# merope-power.net
KiCad netlist of a schematic drawn in EAGLE
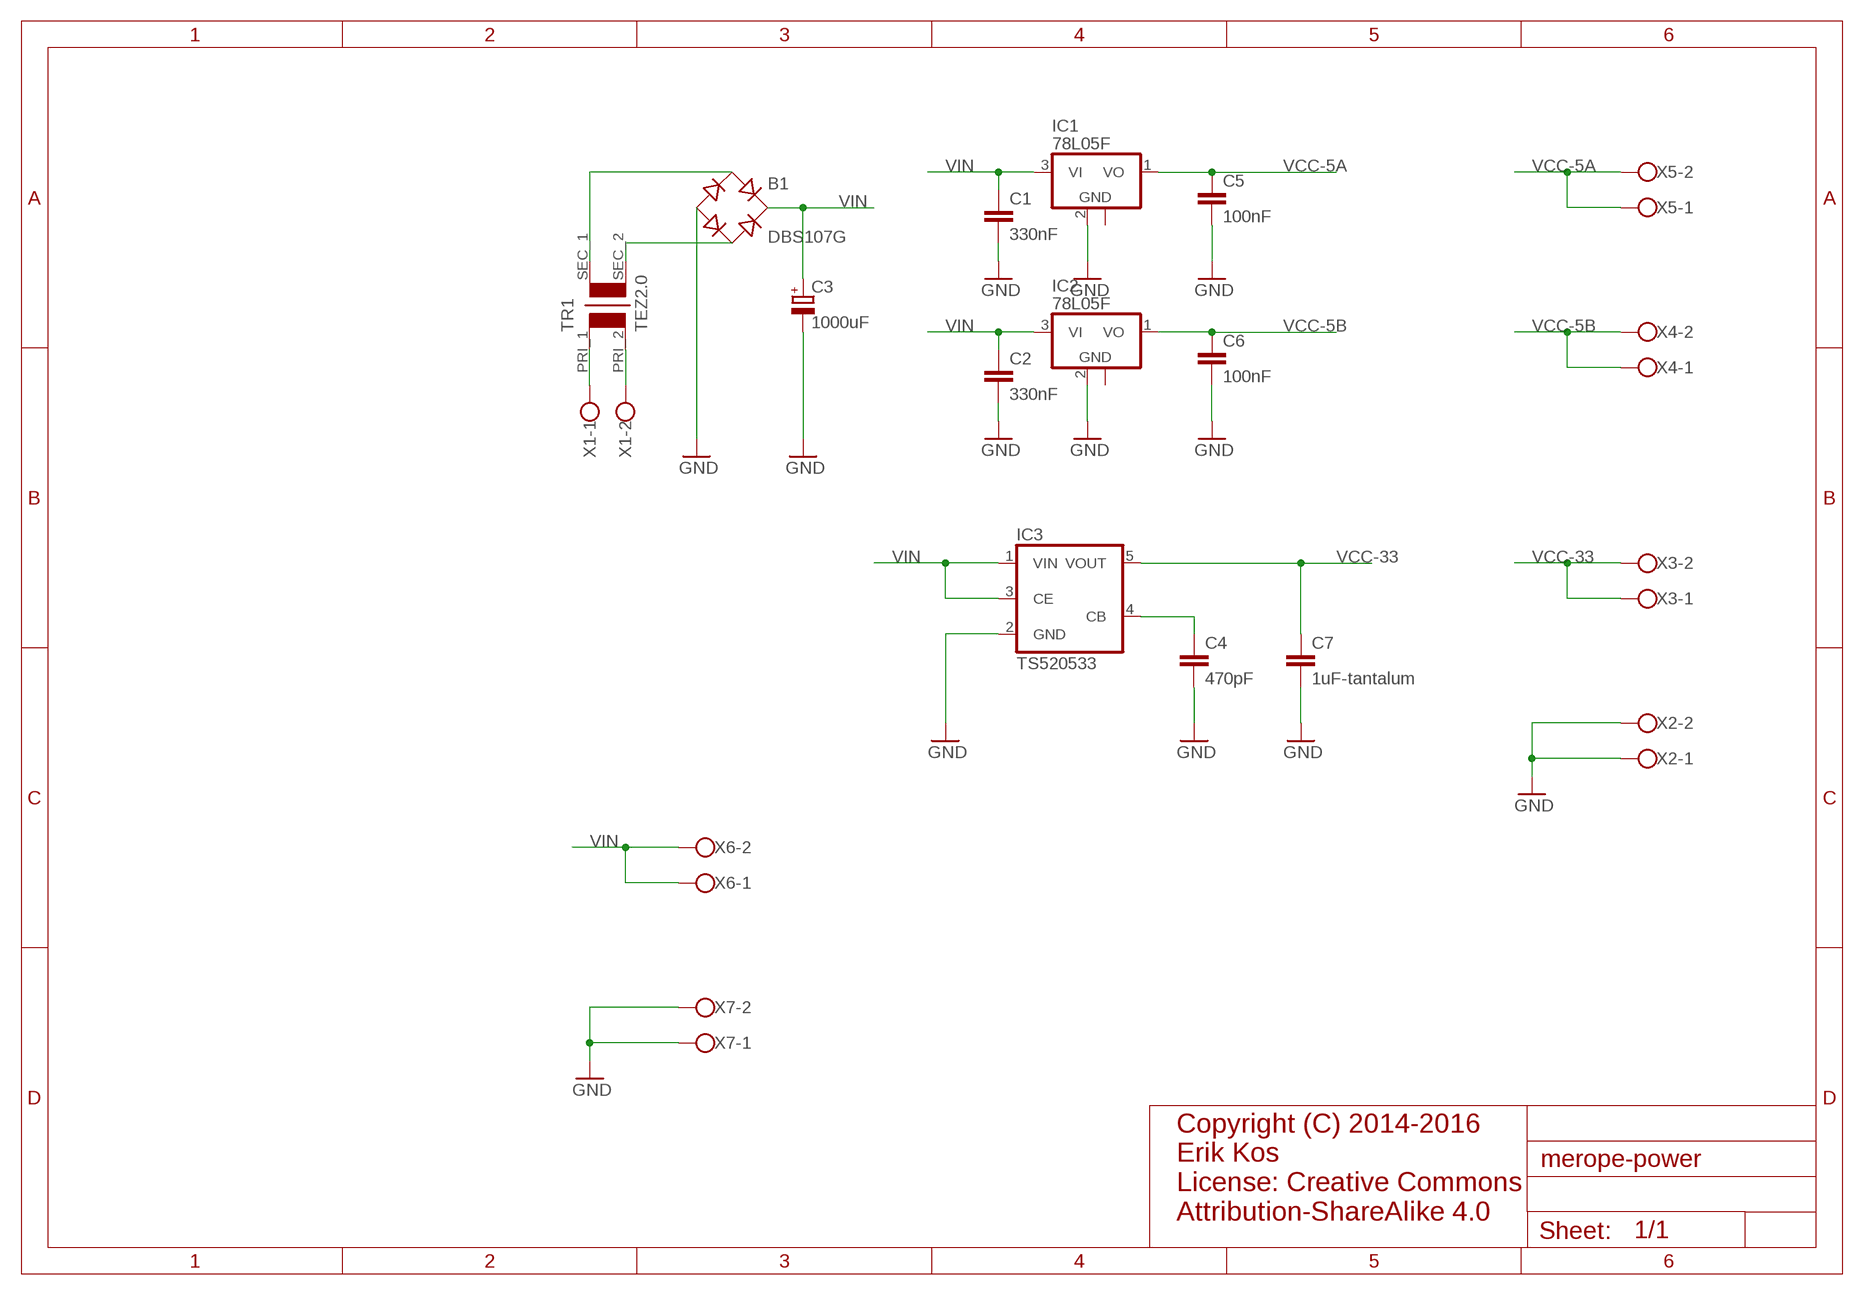
[diagram p0: schematic, sheet 1]

(export (version "E")
  (design (tool "Eeschema 10.0.6"))
  (components
    (comp (ref "B1")
      (value "DBS107G")
      (footprint "eagle-import:DBS")
      (libsource (lib "eagle-import") (part "DB?GS107"))
    )
    (comp (ref "C1")
      (value "330nF")
      (footprint "eagle-import:C0805")
      (libsource (lib "eagle-import") (part "C-EUC0805"))
    )
    (comp (ref "C2")
      (value "330nF")
      (footprint "eagle-import:C0805")
      (libsource (lib "eagle-import") (part "C-EUC0805"))
    )
    (comp (ref "C3")
      (value "1000uF")
      (footprint "eagle-import:TT5D11")
      (libsource (lib "eagle-import") (part "CPOL-EUTT5D11"))
    )
    (comp (ref "C4")
      (value "470pF")
      (footprint "eagle-import:C0805")
      (libsource (lib "eagle-import") (part "C-EUC0805"))
    )
    (comp (ref "C5")
      (value "100nF")
      (footprint "eagle-import:C0805")
      (libsource (lib "eagle-import") (part "C-EUC0805"))
    )
    (comp (ref "C6")
      (value "100nF")
      (footprint "eagle-import:C0805")
      (libsource (lib "eagle-import") (part "C-EUC0805"))
    )
    (comp (ref "C7")
      (value "1uF-tantalum")
      (footprint "eagle-import:C0805")
      (libsource (lib "eagle-import") (part "C-EUC0805"))
    )
    (comp (ref "IC1")
      (value "78L05F")
      (footprint "eagle-import:SOT89")
      (libsource (lib "eagle-import") (part "78LF05"))
    )
    (comp (ref "IC2")
      (value "78L05F")
      (footprint "eagle-import:SOT89")
      (libsource (lib "eagle-import") (part "78LF05"))
    )
    (comp (ref "IC3")
      (value "TS520533")
      (footprint "eagle-import:SOT25")
      (libsource (lib "eagle-import") (part "TS520533"))
    )
    (comp (ref "TR1")
      (value "TEZ2.0")
      (footprint "eagle-import:TEZ2.0")
      (libsource (lib "eagle-import") (part "TEZ2.0"))
    )
    (comp (ref "X1")
      (value "TERMINAL_BLOCK_5_2")
      (footprint "eagle-import:TERMINAL_BLOCK_5_2")
      (libsource (lib "eagle-import") (part "TERMINAL_BLOCK_5_2"))
    )
    (comp (ref "X2")
      (value "TERMINAL_BLOCK_35_2")
      (footprint "eagle-import:TERMINAL_BLOCK_35_2")
      (libsource (lib "eagle-import") (part "TERMINAL_BLOCK_35_2"))
    )
    (comp (ref "X3")
      (value "TERMINAL_BLOCK_35_2")
      (footprint "eagle-import:TERMINAL_BLOCK_35_2")
      (libsource (lib "eagle-import") (part "TERMINAL_BLOCK_35_2"))
    )
    (comp (ref "X4")
      (value "TERMINAL_BLOCK_35_2")
      (footprint "eagle-import:TERMINAL_BLOCK_35_2")
      (libsource (lib "eagle-import") (part "TERMINAL_BLOCK_35_2"))
    )
    (comp (ref "X5")
      (value "TERMINAL_BLOCK_35_2")
      (footprint "eagle-import:TERMINAL_BLOCK_35_2")
      (libsource (lib "eagle-import") (part "TERMINAL_BLOCK_35_2"))
    )
    (comp (ref "X6")
      (value "TERMINAL_BLOCK_35_2")
      (footprint "eagle-import:TERMINAL_BLOCK_35_2")
      (libsource (lib "eagle-import") (part "TERMINAL_BLOCK_35_2"))
    )
    (comp (ref "X7")
      (value "TERMINAL_BLOCK_35_2")
      (footprint "eagle-import:TERMINAL_BLOCK_35_2")
      (libsource (lib "eagle-import") (part "TERMINAL_BLOCK_35_2"))
    )
  )
  (nets
    (net (code "1") (name "/VCC-5A") (class "Default")
      (node (ref "C5") (pin "1") (pinfunction "1_1") (pintype "passive"))
      (node (ref "IC1") (pin "1") (pinfunction "VO_1") (pintype "passive"))
      (node (ref "X5") (pin "1") (pinfunction "KL_1") (pintype "passive"))
      (node (ref "X5") (pin "2") (pinfunction "KL_2") (pintype "passive"))
    )
    (net (code "2") (name "/VCC-5B") (class "Default")
      (node (ref "C6") (pin "1") (pinfunction "1_1") (pintype "passive"))
      (node (ref "IC2") (pin "1") (pinfunction "VO_1") (pintype "passive"))
      (node (ref "X4") (pin "1") (pinfunction "KL_1") (pintype "passive"))
      (node (ref "X4") (pin "2") (pinfunction "KL_2") (pintype "passive"))
    )
    (net (code "3") (name "/VCC-33") (class "Default")
      (node (ref "C7") (pin "1") (pinfunction "1_1") (pintype "passive"))
      (node (ref "IC3") (pin "5") (pinfunction "VOUT_5") (pintype "passive"))
      (node (ref "X3") (pin "1") (pinfunction "KL_1") (pintype "passive"))
      (node (ref "X3") (pin "2") (pinfunction "KL_2") (pintype "passive"))
    )
    (net (code "4") (name "/VIN") (class "Default")
      (node (ref "B1") (pin "+") (pinfunction "+_+") (pintype "passive"))
      (node (ref "C1") (pin "1") (pinfunction "1_1") (pintype "passive"))
      (node (ref "C2") (pin "1") (pinfunction "1_1") (pintype "passive"))
      (node (ref "C3") (pin "+") (pinfunction "+_+") (pintype "passive"))
      (node (ref "IC1") (pin "3") (pinfunction "VI_3") (pintype "input"))
      (node (ref "IC2") (pin "3") (pinfunction "VI_3") (pintype "input"))
      (node (ref "IC3") (pin "1") (pinfunction "VIN_1") (pintype "input"))
      (node (ref "IC3") (pin "3") (pinfunction "CE_3") (pintype "input"))
      (node (ref "X6") (pin "1") (pinfunction "KL_1") (pintype "passive"))
      (node (ref "X6") (pin "2") (pinfunction "KL_2") (pintype "passive"))
    )
    (net (code "5") (name "GND") (class "Default")
      (node (ref "B1") (pin "-") (pinfunction "-_-") (pintype "passive"))
      (node (ref "C1") (pin "2") (pinfunction "2_2") (pintype "passive"))
      (node (ref "C2") (pin "2") (pinfunction "2_2") (pintype "passive"))
      (node (ref "C3") (pin "-") (pinfunction "-_-") (pintype "passive"))
      (node (ref "C4") (pin "2") (pinfunction "2_2") (pintype "passive"))
      (node (ref "C5") (pin "2") (pinfunction "2_2") (pintype "passive"))
      (node (ref "C6") (pin "2") (pinfunction "2_2") (pintype "passive"))
      (node (ref "C7") (pin "2") (pinfunction "2_2") (pintype "passive"))
      (node (ref "IC1") (pin "2") (pinfunction "GND_2") (pintype "passive"))
      (node (ref "IC2") (pin "2") (pinfunction "GND_2") (pintype "passive"))
      (node (ref "IC3") (pin "2") (pinfunction "GND_2") (pintype "passive"))
      (node (ref "X2") (pin "1") (pinfunction "KL_1") (pintype "passive"))
      (node (ref "X2") (pin "2") (pinfunction "KL_2") (pintype "passive"))
      (node (ref "X7") (pin "1") (pinfunction "KL_1") (pintype "passive"))
      (node (ref "X7") (pin "2") (pinfunction "KL_2") (pintype "passive"))
    )
    (net (code "6") (name "Net-(B1-PadAC1)") (class "Default")
      (node (ref "B1") (pin "AC1") (pinfunction "AC1_AC1") (pintype "passive"))
      (node (ref "TR1") (pin "SEC_1") (pinfunction "SEC_1_SEC_1") (pintype "passive"))
    )
    (net (code "7") (name "Net-(B1-PadAC2)") (class "Default")
      (node (ref "B1") (pin "AC2") (pinfunction "AC2_AC2") (pintype "passive"))
      (node (ref "TR1") (pin "SEC_2") (pinfunction "SEC_2_SEC_2") (pintype "passive"))
    )
    (net (code "8") (name "Net-(IC3-CB)") (class "Default")
      (node (ref "C4") (pin "1") (pinfunction "1_1") (pintype "passive"))
      (node (ref "IC3") (pin "4") (pinfunction "CB_4") (pintype "input"))
    )
    (net (code "9") (name "Net-(X1A-KL)") (class "Default")
      (node (ref "TR1") (pin "PRI_1") (pinfunction "PRI_1_PRI_1") (pintype "passive"))
      (node (ref "X1") (pin "1") (pinfunction "KL_1") (pintype "passive"))
    )
    (net (code "10") (name "Net-(X1B-KL)") (class "Default")
      (node (ref "TR1") (pin "PRI_2") (pinfunction "PRI_2_PRI_2") (pintype "passive"))
      (node (ref "X1") (pin "2") (pinfunction "KL_2") (pintype "passive"))
    )
    (net (code "11") (name "unconnected-(IC1-GND-Pad2@1)") (class "Default")
      (node (ref "IC1") (pin "2@1") (pinfunction "GND_2@1") (pintype "passive"))
    )
    (net (code "12") (name "unconnected-(IC2-GND-Pad2@1)") (class "Default")
      (node (ref "IC2") (pin "2@1") (pinfunction "GND_2@1") (pintype "passive"))
    )
  )
)
